# outsim_uno.net
KiCad netlist of a schematic drawn in EAGLE
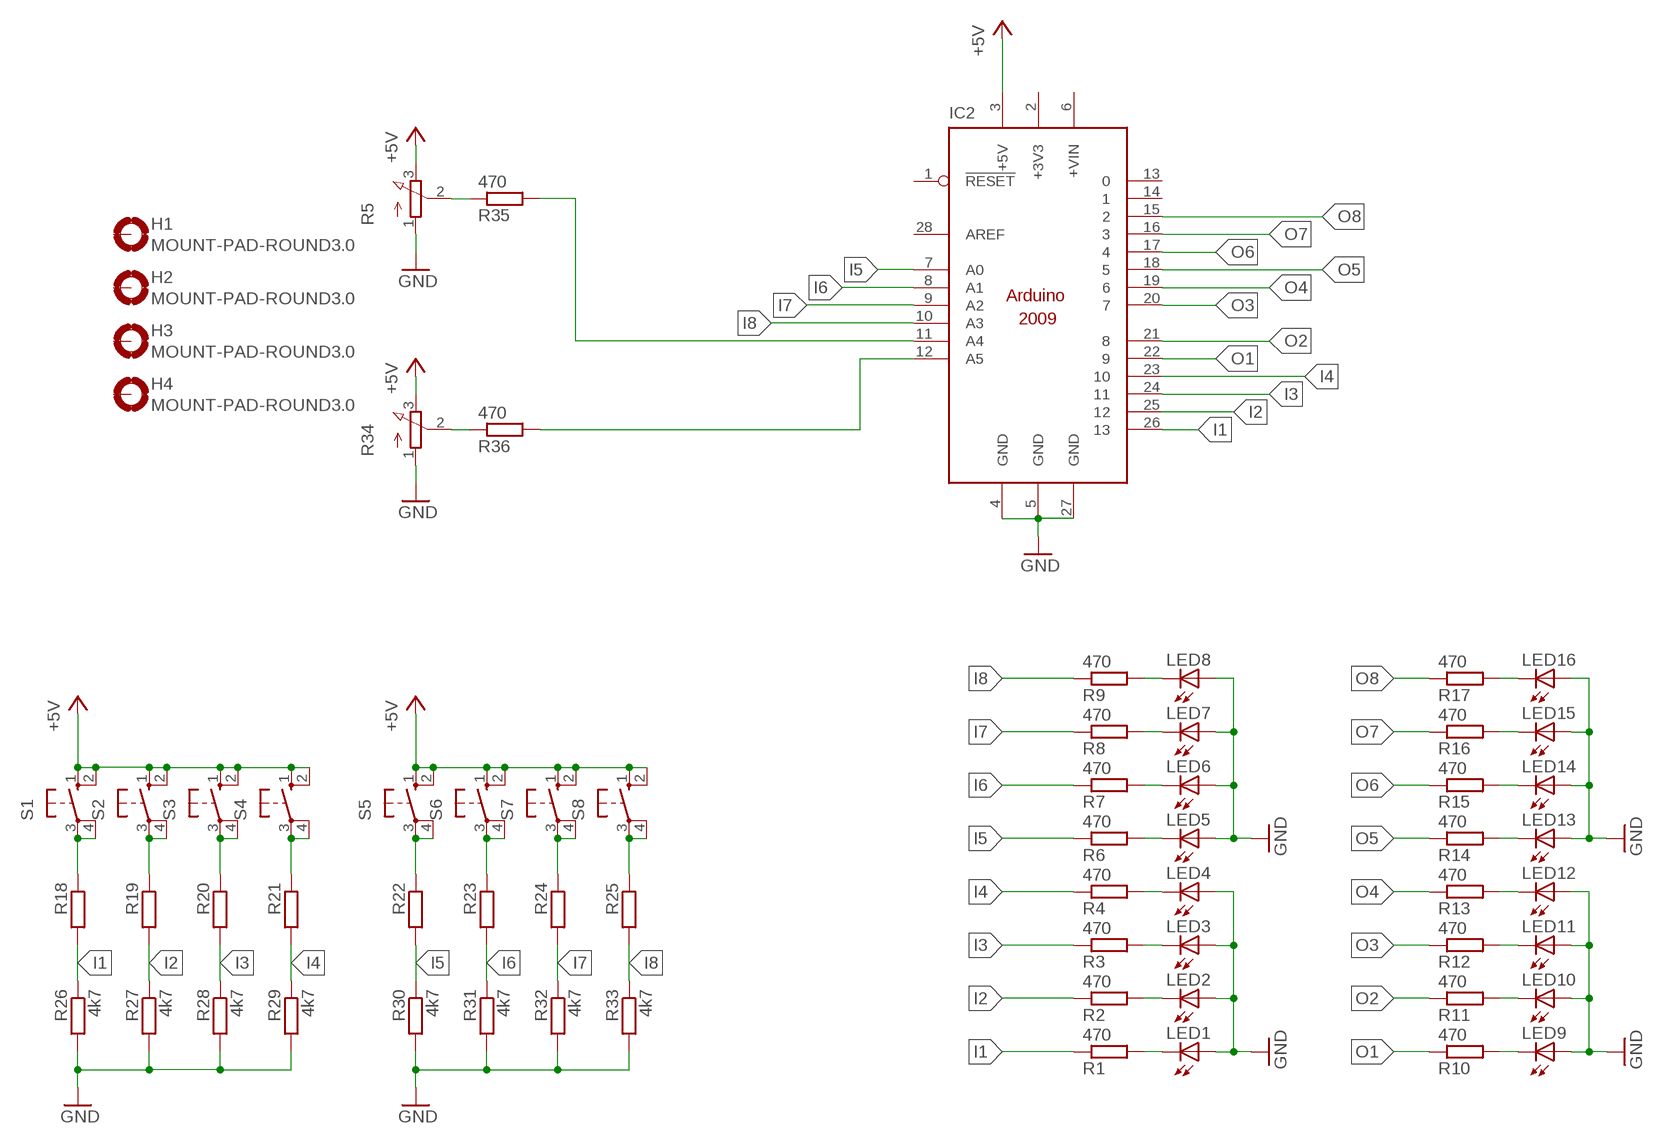
[diagram p0: schematic, sheet 1]

(export (version "E")
  (design (tool "Eeschema 10.0.6"))
  (components
    (comp (ref "H1")
      (value "MOUNT-PAD-ROUND3.0")
      (footprint "eagle-import:3,0-PAD")
      (libsource (lib "eagle-import") (part "MOUNT-PAD-ROUND3.0"))
    )
    (comp (ref "H2")
      (value "MOUNT-PAD-ROUND3.0")
      (footprint "eagle-import:3,0-PAD")
      (libsource (lib "eagle-import") (part "MOUNT-PAD-ROUND3.0"))
    )
    (comp (ref "H3")
      (value "MOUNT-PAD-ROUND3.0")
      (footprint "eagle-import:3,0-PAD")
      (libsource (lib "eagle-import") (part "MOUNT-PAD-ROUND3.0"))
    )
    (comp (ref "H4")
      (value "MOUNT-PAD-ROUND3.0")
      (footprint "eagle-import:3,0-PAD")
      (libsource (lib "eagle-import") (part "MOUNT-PAD-ROUND3.0"))
    )
    (comp (ref "IC2")
      (value "ARDUINO2009_12")
      (footprint "eagle-import:ARDUINO2009_2")
      (libsource (lib "eagle-import") (part "ARDUINO2009_12"))
    )
    (comp (ref "LED1")
      (value "LED5MM")
      (footprint "eagle-import:LED5MM")
      (libsource (lib "eagle-import") (part "LED5MM"))
    )
    (comp (ref "LED2")
      (value "LED5MM")
      (footprint "eagle-import:LED5MM")
      (libsource (lib "eagle-import") (part "LED5MM"))
    )
    (comp (ref "LED3")
      (value "LED5MM")
      (footprint "eagle-import:LED5MM")
      (libsource (lib "eagle-import") (part "LED5MM"))
    )
    (comp (ref "LED4")
      (value "LED5MM")
      (footprint "eagle-import:LED5MM")
      (libsource (lib "eagle-import") (part "LED5MM"))
    )
    (comp (ref "LED5")
      (value "LED5MM")
      (footprint "eagle-import:LED5MM")
      (libsource (lib "eagle-import") (part "LED5MM"))
    )
    (comp (ref "LED6")
      (value "LED5MM")
      (footprint "eagle-import:LED5MM")
      (libsource (lib "eagle-import") (part "LED5MM"))
    )
    (comp (ref "LED7")
      (value "LED5MM")
      (footprint "eagle-import:LED5MM")
      (libsource (lib "eagle-import") (part "LED5MM"))
    )
    (comp (ref "LED8")
      (value "LED5MM")
      (footprint "eagle-import:LED5MM")
      (libsource (lib "eagle-import") (part "LED5MM"))
    )
    (comp (ref "LED9")
      (value "LED5MM")
      (footprint "eagle-import:LED5MM")
      (libsource (lib "eagle-import") (part "LED5MM"))
    )
    (comp (ref "LED10")
      (value "LED5MM")
      (footprint "eagle-import:LED5MM")
      (libsource (lib "eagle-import") (part "LED5MM"))
    )
    (comp (ref "LED11")
      (value "LED5MM")
      (footprint "eagle-import:LED5MM")
      (libsource (lib "eagle-import") (part "LED5MM"))
    )
    (comp (ref "LED12")
      (value "LED5MM")
      (footprint "eagle-import:LED5MM")
      (libsource (lib "eagle-import") (part "LED5MM"))
    )
    (comp (ref "LED13")
      (value "LED5MM")
      (footprint "eagle-import:LED5MM")
      (libsource (lib "eagle-import") (part "LED5MM"))
    )
    (comp (ref "LED14")
      (value "LED5MM")
      (footprint "eagle-import:LED5MM")
      (libsource (lib "eagle-import") (part "LED5MM"))
    )
    (comp (ref "LED15")
      (value "LED5MM")
      (footprint "eagle-import:LED5MM")
      (libsource (lib "eagle-import") (part "LED5MM"))
    )
    (comp (ref "LED16")
      (value "LED5MM")
      (footprint "eagle-import:LED5MM")
      (libsource (lib "eagle-import") (part "LED5MM"))
    )
    (comp (ref "R1")
      (value "470")
      (footprint "eagle-import:0207_10")
      (libsource (lib "eagle-import") (part "R-EU_0207/10"))
    )
    (comp (ref "R2")
      (value "470")
      (footprint "eagle-import:0207_10")
      (libsource (lib "eagle-import") (part "R-EU_0207/10"))
    )
    (comp (ref "R3")
      (value "470")
      (footprint "eagle-import:0207_10")
      (libsource (lib "eagle-import") (part "R-EU_0207/10"))
    )
    (comp (ref "R4")
      (value "470")
      (footprint "eagle-import:0207_10")
      (libsource (lib "eagle-import") (part "R-EU_0207/10"))
    )
    (comp (ref "R5")
      (value "3RP/1610N")
      (footprint "eagle-import:3RP_1610N")
      (libsource (lib "eagle-import") (part "3RP/1610N"))
    )
    (comp (ref "R6")
      (value "470")
      (footprint "eagle-import:0207_10")
      (libsource (lib "eagle-import") (part "R-EU_0207/10"))
    )
    (comp (ref "R7")
      (value "470")
      (footprint "eagle-import:0207_10")
      (libsource (lib "eagle-import") (part "R-EU_0207/10"))
    )
    (comp (ref "R8")
      (value "470")
      (footprint "eagle-import:0207_10")
      (libsource (lib "eagle-import") (part "R-EU_0207/10"))
    )
    (comp (ref "R9")
      (value "470")
      (footprint "eagle-import:0207_10")
      (libsource (lib "eagle-import") (part "R-EU_0207/10"))
    )
    (comp (ref "R10")
      (value "470")
      (footprint "eagle-import:0207_10")
      (libsource (lib "eagle-import") (part "R-EU_0207/10"))
    )
    (comp (ref "R11")
      (value "470")
      (footprint "eagle-import:0207_10")
      (libsource (lib "eagle-import") (part "R-EU_0207/10"))
    )
    (comp (ref "R12")
      (value "470")
      (footprint "eagle-import:0207_10")
      (libsource (lib "eagle-import") (part "R-EU_0207/10"))
    )
    (comp (ref "R13")
      (value "470")
      (footprint "eagle-import:0207_10")
      (libsource (lib "eagle-import") (part "R-EU_0207/10"))
    )
    (comp (ref "R14")
      (value "470")
      (footprint "eagle-import:0207_10")
      (libsource (lib "eagle-import") (part "R-EU_0207/10"))
    )
    (comp (ref "R15")
      (value "470")
      (footprint "eagle-import:0207_10")
      (libsource (lib "eagle-import") (part "R-EU_0207/10"))
    )
    (comp (ref "R16")
      (value "470")
      (footprint "eagle-import:0207_10")
      (libsource (lib "eagle-import") (part "R-EU_0207/10"))
    )
    (comp (ref "R17")
      (value "470")
      (footprint "eagle-import:0207_10")
      (libsource (lib "eagle-import") (part "R-EU_0207/10"))
    )
    (comp (ref "R18")
      (value "R-EU_0207/10")
      (footprint "eagle-import:0207_10")
      (libsource (lib "eagle-import") (part "R-EU_0207/10"))
    )
    (comp (ref "R19")
      (value "R-EU_0207/10")
      (footprint "eagle-import:0207_10")
      (libsource (lib "eagle-import") (part "R-EU_0207/10"))
    )
    (comp (ref "R20")
      (value "R-EU_0207/10")
      (footprint "eagle-import:0207_10")
      (libsource (lib "eagle-import") (part "R-EU_0207/10"))
    )
    (comp (ref "R21")
      (value "R-EU_0207/10")
      (footprint "eagle-import:0207_10")
      (libsource (lib "eagle-import") (part "R-EU_0207/10"))
    )
    (comp (ref "R22")
      (value "R-EU_0207/10")
      (footprint "eagle-import:0207_10")
      (libsource (lib "eagle-import") (part "R-EU_0207/10"))
    )
    (comp (ref "R23")
      (value "R-EU_0207/10")
      (footprint "eagle-import:0207_10")
      (libsource (lib "eagle-import") (part "R-EU_0207/10"))
    )
    (comp (ref "R24")
      (value "R-EU_0207/10")
      (footprint "eagle-import:0207_10")
      (libsource (lib "eagle-import") (part "R-EU_0207/10"))
    )
    (comp (ref "R25")
      (value "R-EU_0207/10")
      (footprint "eagle-import:0207_10")
      (libsource (lib "eagle-import") (part "R-EU_0207/10"))
    )
    (comp (ref "R26")
      (value "4k7")
      (footprint "eagle-import:0207_10")
      (libsource (lib "eagle-import") (part "R-EU_0207/10"))
    )
    (comp (ref "R27")
      (value "4k7")
      (footprint "eagle-import:0207_10")
      (libsource (lib "eagle-import") (part "R-EU_0207/10"))
    )
    (comp (ref "R28")
      (value "4k7")
      (footprint "eagle-import:0207_10")
      (libsource (lib "eagle-import") (part "R-EU_0207/10"))
    )
    (comp (ref "R29")
      (value "4k7")
      (footprint "eagle-import:0207_10")
      (libsource (lib "eagle-import") (part "R-EU_0207/10"))
    )
    (comp (ref "R30")
      (value "4k7")
      (footprint "eagle-import:0207_10")
      (libsource (lib "eagle-import") (part "R-EU_0207/10"))
    )
    (comp (ref "R31")
      (value "4k7")
      (footprint "eagle-import:0207_10")
      (libsource (lib "eagle-import") (part "R-EU_0207/10"))
    )
    (comp (ref "R32")
      (value "4k7")
      (footprint "eagle-import:0207_10")
      (libsource (lib "eagle-import") (part "R-EU_0207/10"))
    )
    (comp (ref "R33")
      (value "4k7")
      (footprint "eagle-import:0207_10")
      (libsource (lib "eagle-import") (part "R-EU_0207/10"))
    )
    (comp (ref "R34")
      (value "3RP/1610N")
      (footprint "eagle-import:3RP_1610N")
      (libsource (lib "eagle-import") (part "3RP/1610N"))
    )
    (comp (ref "R35")
      (value "470")
      (footprint "eagle-import:0207_10")
      (libsource (lib "eagle-import") (part "R-EU_0207/10"))
    )
    (comp (ref "R36")
      (value "470")
      (footprint "eagle-import:0207_10")
      (libsource (lib "eagle-import") (part "R-EU_0207/10"))
    )
    (comp (ref "S1")
      (value "10-XX")
      (footprint "eagle-import:B3F-10XX")
      (fields (field (name "MPN") "B3F-1000"))
      (libsource (lib "eagle-import") (part "10-XX"))
    )
    (comp (ref "S2")
      (value "10-XX")
      (footprint "eagle-import:B3F-10XX")
      (fields (field (name "MPN") "B3F-1000"))
      (libsource (lib "eagle-import") (part "10-XX"))
    )
    (comp (ref "S3")
      (value "10-XX")
      (footprint "eagle-import:B3F-10XX")
      (fields (field (name "MPN") "B3F-1000"))
      (libsource (lib "eagle-import") (part "10-XX"))
    )
    (comp (ref "S4")
      (value "10-XX")
      (footprint "eagle-import:B3F-10XX")
      (fields (field (name "MPN") "B3F-1000"))
      (libsource (lib "eagle-import") (part "10-XX"))
    )
    (comp (ref "S5")
      (value "10-XX")
      (footprint "eagle-import:B3F-10XX")
      (fields (field (name "MPN") "B3F-1000"))
      (libsource (lib "eagle-import") (part "10-XX"))
    )
    (comp (ref "S6")
      (value "10-XX")
      (footprint "eagle-import:B3F-10XX")
      (fields (field (name "MPN") "B3F-1000"))
      (libsource (lib "eagle-import") (part "10-XX"))
    )
    (comp (ref "S7")
      (value "10-XX")
      (footprint "eagle-import:B3F-10XX")
      (fields (field (name "MPN") "B3F-1000"))
      (libsource (lib "eagle-import") (part "10-XX"))
    )
    (comp (ref "S8")
      (value "10-XX")
      (footprint "eagle-import:B3F-10XX")
      (fields (field (name "MPN") "B3F-1000"))
      (libsource (lib "eagle-import") (part "10-XX"))
    )
  )
  (nets
    (net (code "1") (name "+5V") (class "Default")
      (node (ref "IC2") (pin "3") (pinfunction "+5V_3") (pintype "power_in"))
      (node (ref "R34") (pin "3") (pinfunction "E_3") (pintype "passive"))
      (node (ref "R5") (pin "3") (pinfunction "E_3") (pintype "passive"))
      (node (ref "S1") (pin "1") (pinfunction "S_1") (pintype "passive"))
      (node (ref "S1") (pin "2") (pinfunction "S1_2") (pintype "passive"))
      (node (ref "S2") (pin "1") (pinfunction "S_1") (pintype "passive"))
      (node (ref "S2") (pin "2") (pinfunction "S1_2") (pintype "passive"))
      (node (ref "S3") (pin "1") (pinfunction "S_1") (pintype "passive"))
      (node (ref "S3") (pin "2") (pinfunction "S1_2") (pintype "passive"))
      (node (ref "S4") (pin "1") (pinfunction "S_1") (pintype "passive"))
      (node (ref "S4") (pin "2") (pinfunction "S1_2") (pintype "passive"))
      (node (ref "S5") (pin "1") (pinfunction "S_1") (pintype "passive"))
      (node (ref "S5") (pin "2") (pinfunction "S1_2") (pintype "passive"))
      (node (ref "S6") (pin "1") (pinfunction "S_1") (pintype "passive"))
      (node (ref "S6") (pin "2") (pinfunction "S1_2") (pintype "passive"))
      (node (ref "S7") (pin "1") (pinfunction "S_1") (pintype "passive"))
      (node (ref "S7") (pin "2") (pinfunction "S1_2") (pintype "passive"))
      (node (ref "S8") (pin "1") (pinfunction "S_1") (pintype "passive"))
      (node (ref "S8") (pin "2") (pinfunction "S1_2") (pintype "passive"))
    )
    (net (code "2") (name "/+3V3") (class "Default")
      (node (ref "IC2") (pin "2") (pinfunction "+3V3_2") (pintype "power_in"))
    )
    (net (code "3") (name "GND") (class "Default")
      (node (ref "IC2") (pin "27") (pinfunction "GND_27") (pintype "power_in"))
      (node (ref "IC2") (pin "4") (pinfunction "GND_4") (pintype "power_in"))
      (node (ref "IC2") (pin "5") (pinfunction "GND_5") (pintype "power_in"))
      (node (ref "LED1") (pin "A") (pinfunction "A_A") (pintype "passive"))
      (node (ref "LED10") (pin "A") (pinfunction "A_A") (pintype "passive"))
      (node (ref "LED11") (pin "A") (pinfunction "A_A") (pintype "passive"))
      (node (ref "LED12") (pin "A") (pinfunction "A_A") (pintype "passive"))
      (node (ref "LED13") (pin "A") (pinfunction "A_A") (pintype "passive"))
      (node (ref "LED14") (pin "A") (pinfunction "A_A") (pintype "passive"))
      (node (ref "LED15") (pin "A") (pinfunction "A_A") (pintype "passive"))
      (node (ref "LED16") (pin "A") (pinfunction "A_A") (pintype "passive"))
      (node (ref "LED2") (pin "A") (pinfunction "A_A") (pintype "passive"))
      (node (ref "LED3") (pin "A") (pinfunction "A_A") (pintype "passive"))
      (node (ref "LED4") (pin "A") (pinfunction "A_A") (pintype "passive"))
      (node (ref "LED5") (pin "A") (pinfunction "A_A") (pintype "passive"))
      (node (ref "LED6") (pin "A") (pinfunction "A_A") (pintype "passive"))
      (node (ref "LED7") (pin "A") (pinfunction "A_A") (pintype "passive"))
      (node (ref "LED8") (pin "A") (pinfunction "A_A") (pintype "passive"))
      (node (ref "LED9") (pin "A") (pinfunction "A_A") (pintype "passive"))
      (node (ref "R26") (pin "2") (pinfunction "2_2") (pintype "passive"))
      (node (ref "R27") (pin "2") (pinfunction "2_2") (pintype "passive"))
      (node (ref "R28") (pin "2") (pinfunction "2_2") (pintype "passive"))
      (node (ref "R29") (pin "2") (pinfunction "2_2") (pintype "passive"))
      (node (ref "R30") (pin "2") (pinfunction "2_2") (pintype "passive"))
      (node (ref "R31") (pin "2") (pinfunction "2_2") (pintype "passive"))
      (node (ref "R32") (pin "2") (pinfunction "2_2") (pintype "passive"))
      (node (ref "R33") (pin "2") (pinfunction "2_2") (pintype "passive"))
      (node (ref "R34") (pin "1") (pinfunction "A_1") (pintype "passive"))
      (node (ref "R5") (pin "1") (pinfunction "A_1") (pintype "passive"))
    )
    (net (code "4") (name "I1") (class "Default")
      (node (ref "IC2") (pin "26") (pinfunction "13_26") (pintype "bidirectional"))
      (node (ref "R1") (pin "1") (pinfunction "1_1") (pintype "passive"))
      (node (ref "R18") (pin "2") (pinfunction "2_2") (pintype "passive"))
      (node (ref "R26") (pin "1") (pinfunction "1_1") (pintype "passive"))
    )
    (net (code "5") (name "I2") (class "Default")
      (node (ref "IC2") (pin "25") (pinfunction "12_25") (pintype "bidirectional"))
      (node (ref "R19") (pin "2") (pinfunction "2_2") (pintype "passive"))
      (node (ref "R2") (pin "1") (pinfunction "1_1") (pintype "passive"))
      (node (ref "R27") (pin "1") (pinfunction "1_1") (pintype "passive"))
    )
    (net (code "6") (name "I3") (class "Default")
      (node (ref "IC2") (pin "24") (pinfunction "11_24") (pintype "bidirectional"))
      (node (ref "R20") (pin "2") (pinfunction "2_2") (pintype "passive"))
      (node (ref "R28") (pin "1") (pinfunction "1_1") (pintype "passive"))
      (node (ref "R3") (pin "1") (pinfunction "1_1") (pintype "passive"))
    )
    (net (code "7") (name "I4") (class "Default")
      (node (ref "IC2") (pin "23") (pinfunction "10_23") (pintype "bidirectional"))
      (node (ref "R21") (pin "2") (pinfunction "2_2") (pintype "passive"))
      (node (ref "R29") (pin "1") (pinfunction "1_1") (pintype "passive"))
      (node (ref "R4") (pin "1") (pinfunction "1_1") (pintype "passive"))
    )
    (net (code "8") (name "I5") (class "Default")
      (node (ref "IC2") (pin "7") (pinfunction "A0_7") (pintype "bidirectional"))
      (node (ref "R22") (pin "2") (pinfunction "2_2") (pintype "passive"))
      (node (ref "R30") (pin "1") (pinfunction "1_1") (pintype "passive"))
      (node (ref "R6") (pin "1") (pinfunction "1_1") (pintype "passive"))
    )
    (net (code "9") (name "I6") (class "Default")
      (node (ref "IC2") (pin "8") (pinfunction "A1_8") (pintype "bidirectional"))
      (node (ref "R23") (pin "2") (pinfunction "2_2") (pintype "passive"))
      (node (ref "R31") (pin "1") (pinfunction "1_1") (pintype "passive"))
      (node (ref "R7") (pin "1") (pinfunction "1_1") (pintype "passive"))
    )
    (net (code "10") (name "I7") (class "Default")
      (node (ref "IC2") (pin "9") (pinfunction "A2_9") (pintype "bidirectional"))
      (node (ref "R24") (pin "2") (pinfunction "2_2") (pintype "passive"))
      (node (ref "R32") (pin "1") (pinfunction "1_1") (pintype "passive"))
      (node (ref "R8") (pin "1") (pinfunction "1_1") (pintype "passive"))
    )
    (net (code "11") (name "I8") (class "Default")
      (node (ref "IC2") (pin "10") (pinfunction "A3_10") (pintype "bidirectional"))
      (node (ref "R25") (pin "2") (pinfunction "2_2") (pintype "passive"))
      (node (ref "R33") (pin "1") (pinfunction "1_1") (pintype "passive"))
      (node (ref "R9") (pin "1") (pinfunction "1_1") (pintype "passive"))
    )
    (net (code "12") (name "Net-(IC2-A4)") (class "Default")
      (node (ref "IC2") (pin "11") (pinfunction "A4_11") (pintype "bidirectional"))
      (node (ref "R35") (pin "2") (pinfunction "2_2") (pintype "passive"))
    )
    (net (code "13") (name "Net-(IC2-A5)") (class "Default")
      (node (ref "IC2") (pin "12") (pinfunction "A5_12") (pintype "bidirectional"))
      (node (ref "R36") (pin "2") (pinfunction "2_2") (pintype "passive"))
    )
    (net (code "14") (name "Net-(LED1-C)") (class "Default")
      (node (ref "LED1") (pin "K") (pinfunction "C_K") (pintype "passive"))
      (node (ref "R1") (pin "2") (pinfunction "2_2") (pintype "passive"))
    )
    (net (code "15") (name "Net-(LED2-C)") (class "Default")
      (node (ref "LED2") (pin "K") (pinfunction "C_K") (pintype "passive"))
      (node (ref "R2") (pin "2") (pinfunction "2_2") (pintype "passive"))
    )
    (net (code "16") (name "Net-(LED3-C)") (class "Default")
      (node (ref "LED3") (pin "K") (pinfunction "C_K") (pintype "passive"))
      (node (ref "R3") (pin "2") (pinfunction "2_2") (pintype "passive"))
    )
    (net (code "17") (name "Net-(LED4-C)") (class "Default")
      (node (ref "LED4") (pin "K") (pinfunction "C_K") (pintype "passive"))
      (node (ref "R4") (pin "2") (pinfunction "2_2") (pintype "passive"))
    )
    (net (code "18") (name "Net-(LED5-C)") (class "Default")
      (node (ref "LED5") (pin "K") (pinfunction "C_K") (pintype "passive"))
      (node (ref "R6") (pin "2") (pinfunction "2_2") (pintype "passive"))
    )
    (net (code "19") (name "Net-(LED6-C)") (class "Default")
      (node (ref "LED6") (pin "K") (pinfunction "C_K") (pintype "passive"))
      (node (ref "R7") (pin "2") (pinfunction "2_2") (pintype "passive"))
    )
    (net (code "20") (name "Net-(LED7-C)") (class "Default")
      (node (ref "LED7") (pin "K") (pinfunction "C_K") (pintype "passive"))
      (node (ref "R8") (pin "2") (pinfunction "2_2") (pintype "passive"))
    )
    (net (code "21") (name "Net-(LED8-C)") (class "Default")
      (node (ref "LED8") (pin "K") (pinfunction "C_K") (pintype "passive"))
      (node (ref "R9") (pin "2") (pinfunction "2_2") (pintype "passive"))
    )
    (net (code "22") (name "Net-(LED9-C)") (class "Default")
      (node (ref "LED9") (pin "K") (pinfunction "C_K") (pintype "passive"))
      (node (ref "R10") (pin "2") (pinfunction "2_2") (pintype "passive"))
    )
    (net (code "23") (name "Net-(LED10-C)") (class "Default")
      (node (ref "LED10") (pin "K") (pinfunction "C_K") (pintype "passive"))
      (node (ref "R11") (pin "2") (pinfunction "2_2") (pintype "passive"))
    )
    (net (code "24") (name "Net-(LED11-C)") (class "Default")
      (node (ref "LED11") (pin "K") (pinfunction "C_K") (pintype "passive"))
      (node (ref "R12") (pin "2") (pinfunction "2_2") (pintype "passive"))
    )
    (net (code "25") (name "Net-(LED12-C)") (class "Default")
      (node (ref "LED12") (pin "K") (pinfunction "C_K") (pintype "passive"))
      (node (ref "R13") (pin "2") (pinfunction "2_2") (pintype "passive"))
    )
    (net (code "26") (name "Net-(LED13-C)") (class "Default")
      (node (ref "LED13") (pin "K") (pinfunction "C_K") (pintype "passive"))
      (node (ref "R14") (pin "2") (pinfunction "2_2") (pintype "passive"))
    )
    (net (code "27") (name "Net-(LED14-C)") (class "Default")
      (node (ref "LED14") (pin "K") (pinfunction "C_K") (pintype "passive"))
      (node (ref "R15") (pin "2") (pinfunction "2_2") (pintype "passive"))
    )
    (net (code "28") (name "Net-(LED15-C)") (class "Default")
      (node (ref "LED15") (pin "K") (pinfunction "C_K") (pintype "passive"))
      (node (ref "R16") (pin "2") (pinfunction "2_2") (pintype "passive"))
    )
    (net (code "29") (name "Net-(LED16-C)") (class "Default")
      (node (ref "LED16") (pin "K") (pinfunction "C_K") (pintype "passive"))
      (node (ref "R17") (pin "2") (pinfunction "2_2") (pintype "passive"))
    )
    (net (code "30") (name "Net-(R5-S)") (class "Default")
      (node (ref "R35") (pin "1") (pinfunction "1_1") (pintype "passive"))
      (node (ref "R5") (pin "2") (pinfunction "S_2") (pintype "passive"))
    )
    (net (code "31") (name "Net-(R34-S)") (class "Default")
      (node (ref "R34") (pin "2") (pinfunction "S_2") (pintype "passive"))
      (node (ref "R36") (pin "1") (pinfunction "1_1") (pintype "passive"))
    )
    (net (code "32") (name "Net-(S1-P)") (class "Default")
      (node (ref "R18") (pin "1") (pinfunction "1_1") (pintype "passive"))
      (node (ref "S1") (pin "3") (pinfunction "P_3") (pintype "passive"))
      (node (ref "S1") (pin "4") (pinfunction "P1_4") (pintype "passive"))
    )
    (net (code "33") (name "Net-(S2-P)") (class "Default")
      (node (ref "R19") (pin "1") (pinfunction "1_1") (pintype "passive"))
      (node (ref "S2") (pin "3") (pinfunction "P_3") (pintype "passive"))
      (node (ref "S2") (pin "4") (pinfunction "P1_4") (pintype "passive"))
    )
    (net (code "34") (name "Net-(S3-P)") (class "Default")
      (node (ref "R20") (pin "1") (pinfunction "1_1") (pintype "passive"))
      (node (ref "S3") (pin "3") (pinfunction "P_3") (pintype "passive"))
      (node (ref "S3") (pin "4") (pinfunction "P1_4") (pintype "passive"))
    )
    (net (code "35") (name "Net-(S4-P)") (class "Default")
      (node (ref "R21") (pin "1") (pinfunction "1_1") (pintype "passive"))
      (node (ref "S4") (pin "3") (pinfunction "P_3") (pintype "passive"))
      (node (ref "S4") (pin "4") (pinfunction "P1_4") (pintype "passive"))
    )
    (net (code "36") (name "Net-(S5-P)") (class "Default")
      (node (ref "R22") (pin "1") (pinfunction "1_1") (pintype "passive"))
      (node (ref "S5") (pin "3") (pinfunction "P_3") (pintype "passive"))
      (node (ref "S5") (pin "4") (pinfunction "P1_4") (pintype "passive"))
    )
    (net (code "37") (name "Net-(S6-P)") (class "Default")
      (node (ref "R23") (pin "1") (pinfunction "1_1") (pintype "passive"))
      (node (ref "S6") (pin "3") (pinfunction "P_3") (pintype "passive"))
      (node (ref "S6") (pin "4") (pinfunction "P1_4") (pintype "passive"))
    )
    (net (code "38") (name "Net-(S7-P)") (class "Default")
      (node (ref "R24") (pin "1") (pinfunction "1_1") (pintype "passive"))
      (node (ref "S7") (pin "3") (pinfunction "P_3") (pintype "passive"))
      (node (ref "S7") (pin "4") (pinfunction "P1_4") (pintype "passive"))
    )
    (net (code "39") (name "Net-(S8-P)") (class "Default")
      (node (ref "R25") (pin "1") (pinfunction "1_1") (pintype "passive"))
      (node (ref "S8") (pin "3") (pinfunction "P_3") (pintype "passive"))
      (node (ref "S8") (pin "4") (pinfunction "P1_4") (pintype "passive"))
    )
    (net (code "40") (name "O1") (class "Default")
      (node (ref "IC2") (pin "22") (pinfunction "9_22") (pintype "bidirectional"))
      (node (ref "R10") (pin "1") (pinfunction "1_1") (pintype "passive"))
    )
    (net (code "41") (name "O2") (class "Default")
      (node (ref "IC2") (pin "21") (pinfunction "8_21") (pintype "bidirectional"))
      (node (ref "R11") (pin "1") (pinfunction "1_1") (pintype "passive"))
    )
    (net (code "42") (name "O3") (class "Default")
      (node (ref "IC2") (pin "20") (pinfunction "7_20") (pintype "bidirectional"))
      (node (ref "R12") (pin "1") (pinfunction "1_1") (pintype "passive"))
    )
    (net (code "43") (name "O4") (class "Default")
      (node (ref "IC2") (pin "19") (pinfunction "6_19") (pintype "bidirectional"))
      (node (ref "R13") (pin "1") (pinfunction "1_1") (pintype "passive"))
    )
    (net (code "44") (name "O5") (class "Default")
      (node (ref "IC2") (pin "18") (pinfunction "5_18") (pintype "bidirectional"))
      (node (ref "R14") (pin "1") (pinfunction "1_1") (pintype "passive"))
    )
    (net (code "45") (name "O6") (class "Default")
      (node (ref "IC2") (pin "17") (pinfunction "4_17") (pintype "bidirectional"))
      (node (ref "R15") (pin "1") (pinfunction "1_1") (pintype "passive"))
    )
    (net (code "46") (name "O7") (class "Default")
      (node (ref "IC2") (pin "16") (pinfunction "3_16") (pintype "bidirectional"))
      (node (ref "R16") (pin "1") (pinfunction "1_1") (pintype "passive"))
    )
    (net (code "47") (name "O8") (class "Default")
      (node (ref "IC2") (pin "15") (pinfunction "2_15") (pintype "bidirectional"))
      (node (ref "R17") (pin "1") (pinfunction "1_1") (pintype "passive"))
    )
    (net (code "48") (name "unconnected-(H1-MOUNT-PadB3,0)") (class "Default")
      (node (ref "H1") (pin "B3,0") (pinfunction "MOUNT_B3,0") (pintype "passive"))
    )
    (net (code "49") (name "unconnected-(H2-MOUNT-PadB3,0)") (class "Default")
      (node (ref "H2") (pin "B3,0") (pinfunction "MOUNT_B3,0") (pintype "passive"))
    )
    (net (code "50") (name "unconnected-(H3-MOUNT-PadB3,0)") (class "Default")
      (node (ref "H3") (pin "B3,0") (pinfunction "MOUNT_B3,0") (pintype "passive"))
    )
    (net (code "51") (name "unconnected-(H4-MOUNT-PadB3,0)") (class "Default")
      (node (ref "H4") (pin "B3,0") (pinfunction "MOUNT_B3,0") (pintype "passive"))
    )
    (net (code "52") (name "unconnected-(IC2-+VIN-Pad6)") (class "Default")
      (node (ref "IC2") (pin "6") (pinfunction "+VIN_6") (pintype "bidirectional"))
    )
    (net (code "53") (name "unconnected-(IC2-0-Pad13)") (class "Default")
      (node (ref "IC2") (pin "13") (pinfunction "0_13") (pintype "bidirectional"))
    )
    (net (code "54") (name "unconnected-(IC2-1-Pad14)") (class "Default")
      (node (ref "IC2") (pin "14") (pinfunction "1_14") (pintype "bidirectional"))
    )
    (net (code "55") (name "unconnected-(IC2-AREF-Pad28)") (class "Default")
      (node (ref "IC2") (pin "28") (pinfunction "AREF_28") (pintype "bidirectional"))
    )
    (net (code "56") (name "unconnected-(IC2-~{RESET}-Pad1)") (class "Default")
      (node (ref "IC2") (pin "1") (pinfunction "~{RESET}_1") (pintype "bidirectional"))
    )
  )
)
